# MICROCONTROLLER.net
KiCad netlist of a schematic drawn in Altium Designer
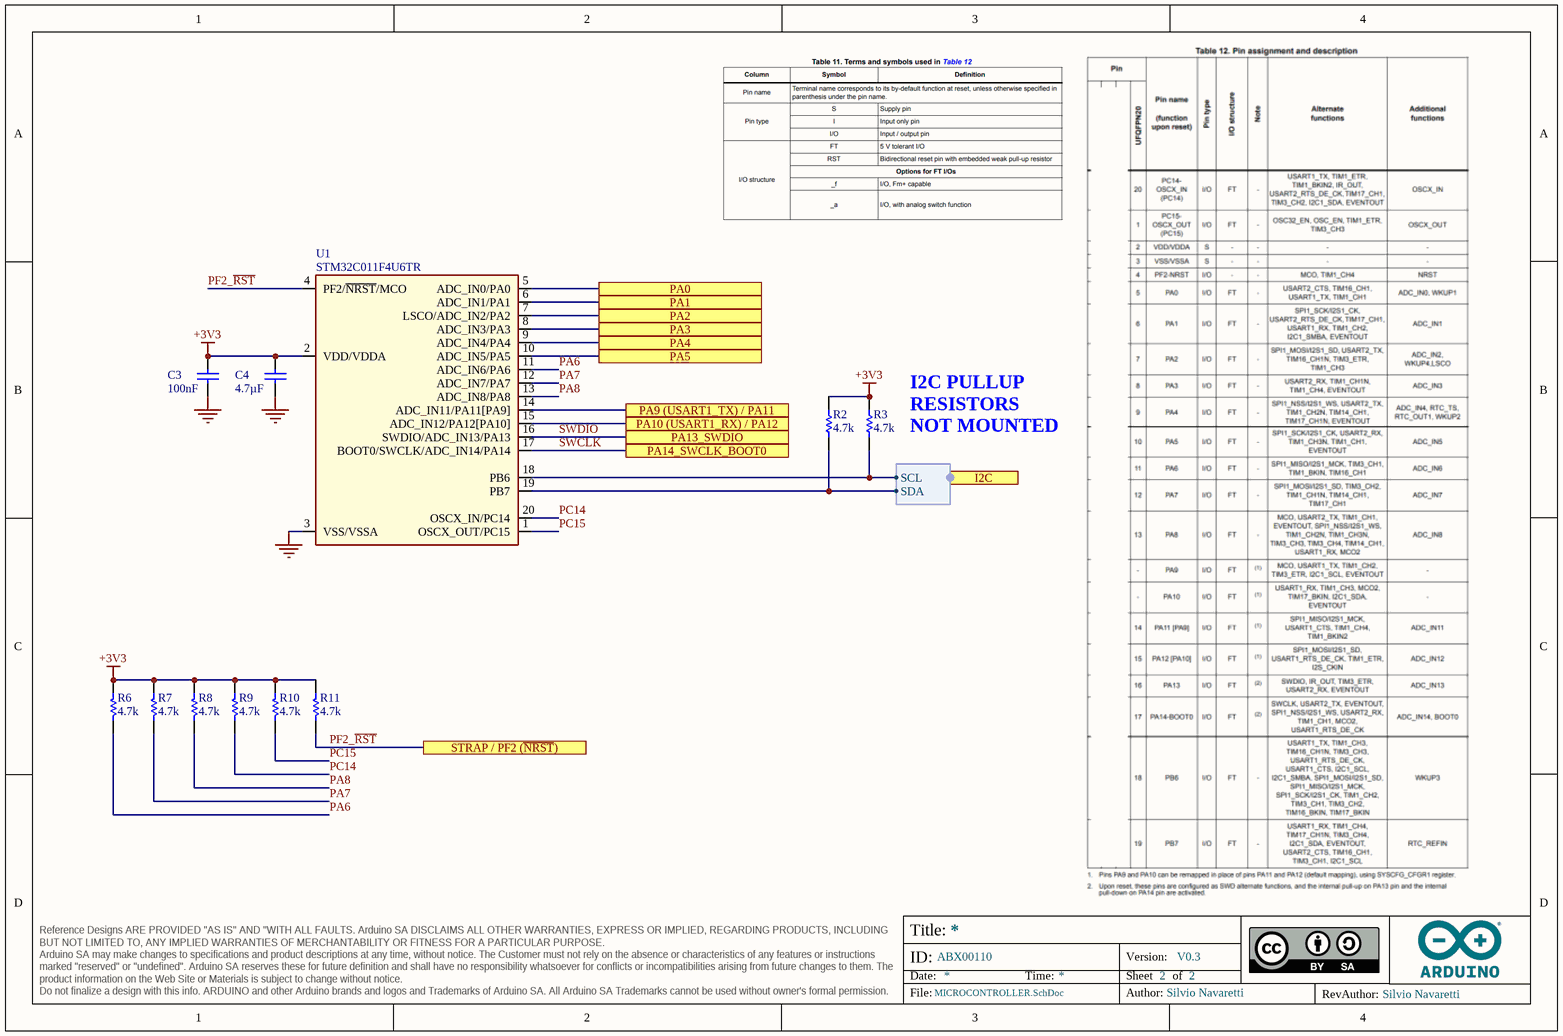
[diagram p0: MICROCONTROLLER.SchDoc]

(export (version "E")
  (design (tool "Eeschema 10.0.6"))
  (components
    (comp (ref "C3")
      (value "100nF")
      (footprint "CAP-0402")
      (description "CAP CHIP 0402 100nF 10% 16V X7R")
      (fields (field (name "MANUFACTURER") "Walsin") (field (name "PART NUMBER") "0402B104K160CT"))
      (libsource (lib "Clean") (part "CAP"))
    )
    (comp (ref "C4")
      (value "4.7µF")
      (footprint "CAP-0603")
      (description "CAP CHIP 0603 4.7uF 10% 16V X5R")
      (fields (field (name "MANUFACTURER") "Murata") (field (name "PART NUMBER") "GRM188R61C475KAAJD"))
      (libsource (lib "Clean") (part "CAP"))
    )
    (comp (ref "R2")
      (value "4.7k")
      (footprint "RES-0402")
      (description "RES CHIP 0402 4k7 1% 1/16W")
      (fields (field (name "PART NUMBER") "RC0402FR-074K7L") (field (name "TOLERANCE") "1%"))
      (libsource (lib "Clean") (part "RES"))
    )
    (comp (ref "R3")
      (value "4.7k")
      (footprint "RES-0402")
      (description "RES CHIP 0402 4k7 1% 1/16W")
      (fields (field (name "PART NUMBER") "RC0402FR-074K7L") (field (name "TOLERANCE") "1%"))
      (libsource (lib "Clean") (part "RES"))
    )
    (comp (ref "R6")
      (value "4.7k")
      (footprint "RES-0402")
      (description "RES CHIP 0402 4k7 1% 1/16W")
      (fields (field (name "POWER") "62.5mW") (field (name "TOLERANCE") "1%"))
      (libsource (lib "Clean") (part "RES"))
    )
    (comp (ref "R7")
      (value "4.7k")
      (footprint "RES-0402")
      (description "RES CHIP 0402 4k7 1% 1/16W")
      (fields (field (name "POWER") "62.5mW") (field (name "TOLERANCE") "1%"))
      (libsource (lib "Clean") (part "RES"))
    )
    (comp (ref "R8")
      (value "4.7k")
      (footprint "RES-0402")
      (description "RES CHIP 0402 4k7 1% 1/16W")
      (fields (field (name "POWER") "62.5mW") (field (name "TOLERANCE") "1%"))
      (libsource (lib "Clean") (part "RES"))
    )
    (comp (ref "R9")
      (value "4.7k")
      (footprint "RES-0402")
      (description "RES CHIP 0402 4k7 1% 1/16W")
      (fields (field (name "POWER") "62.5mW") (field (name "TOLERANCE") "1%"))
      (libsource (lib "Clean") (part "RES"))
    )
    (comp (ref "R10")
      (value "4.7k")
      (footprint "RES-0402")
      (description "RES CHIP 0402 4k7 1% 1/16W")
      (fields (field (name "POWER") "62.5mW") (field (name "TOLERANCE") "1%"))
      (libsource (lib "Clean") (part "RES"))
    )
    (comp (ref "R11")
      (value "4.7k")
      (footprint "RES-0402")
      (description "RES CHIP 0402 4k7 1% 1/16W")
      (fields (field (name "POWER") "62.5mW") (field (name "TOLERANCE") "1%"))
      (libsource (lib "Clean") (part "RES"))
    )
    (comp (ref "U1")
      (value "STM32C011F4U6TR")
      (footprint "UFQFPN20")
      (description "IC Cortex M0, 32b MCU, 32KB Flash, 6KB RAM, VDD 2-3.6V, -40°C to 85°C, QFN20 3x3mm")
      (fields (field (name "MANUFACTURER") "ST Microelectronics"))
      (libsource (lib "Clean") (part "STM32C011F4U6TR"))
    )
  )
  (nets
    (net (code "2") (name "+3V3") (class "Default")
      (node (ref "C3") (pin "1") (pinfunction "1_1") (pintype "passive"))
      (node (ref "C4") (pin "2") (pinfunction "2_2") (pintype "passive"))
      (node (ref "R10") (pin "1") (pinfunction "1_1") (pintype "passive"))
      (node (ref "R11") (pin "1") (pinfunction "1_1") (pintype "passive"))
      (node (ref "R2") (pin "2") (pinfunction "2_2") (pintype "passive"))
      (node (ref "R3") (pin "2") (pinfunction "2_2") (pintype "passive"))
      (node (ref "R6") (pin "1") (pinfunction "1_1") (pintype "passive"))
      (node (ref "R7") (pin "1") (pinfunction "1_1") (pintype "passive"))
      (node (ref "R8") (pin "1") (pinfunction "1_1") (pintype "passive"))
      (node (ref "R9") (pin "1") (pinfunction "1_1") (pintype "passive"))
      (node (ref "U1") (pin "2") (pinfunction "VDD/VDDA_2") (pintype "passive"))
    )
    (net (code "3") (name "/PA0") (class "Default")
      (node (ref "U1") (pin "5") (pinfunction "ADC_IN0/PA0_5") (pintype "passive"))
    )
    (net (code "4") (name "/PA1") (class "Default")
      (node (ref "U1") (pin "6") (pinfunction "ADC_IN1/PA1_6") (pintype "passive"))
    )
    (net (code "5") (name "/PA2") (class "Default")
      (node (ref "U1") (pin "7") (pinfunction "LSCO/ADC_IN2/PA2_7") (pintype "passive"))
    )
    (net (code "6") (name "/PA3") (class "Default")
      (node (ref "U1") (pin "8") (pinfunction "ADC_IN3/PA3_8") (pintype "passive"))
    )
    (net (code "7") (name "/PA4") (class "Default")
      (node (ref "U1") (pin "9") (pinfunction "ADC_IN4/PA4_9") (pintype "passive"))
    )
    (net (code "8") (name "/PA5") (class "Default")
      (node (ref "U1") (pin "10") (pinfunction "ADC_IN5/PA5_10") (pintype "passive"))
    )
    (net (code "9") (name "/PA6") (class "Default")
      (node (ref "R6") (pin "2") (pinfunction "2_2") (pintype "passive"))
      (node (ref "U1") (pin "11") (pinfunction "ADC_IN6/PA6_11") (pintype "passive"))
    )
    (net (code "10") (name "/PA7") (class "Default")
      (node (ref "R7") (pin "2") (pinfunction "2_2") (pintype "passive"))
      (node (ref "U1") (pin "12") (pinfunction "ADC_IN7/PA7_12") (pintype "passive"))
    )
    (net (code "11") (name "/PA8") (class "Default")
      (node (ref "R8") (pin "2") (pinfunction "2_2") (pintype "passive"))
      (node (ref "U1") (pin "13") (pinfunction "ADC_IN8/PA8_13") (pintype "passive"))
    )
    (net (code "12") (name "/PA9 (USART1_TX) {slash} PA11") (class "Default")
      (node (ref "U1") (pin "14") (pinfunction "ADC_IN11/PA11[PA9]_14") (pintype "passive"))
    )
    (net (code "13") (name "/PA10 (USART1_RX) {slash} PA12") (class "Default")
      (node (ref "U1") (pin "15") (pinfunction "ADC_IN12/PA12[PA10]_15") (pintype "passive"))
    )
    (net (code "14") (name "/PC14") (class "Default")
      (node (ref "R9") (pin "2") (pinfunction "2_2") (pintype "passive"))
      (node (ref "U1") (pin "20") (pinfunction "OSCX_IN/PC14_20") (pintype "passive"))
    )
    (net (code "15") (name "/PC15") (class "Default")
      (node (ref "R10") (pin "2") (pinfunction "2_2") (pintype "passive"))
      (node (ref "U1") (pin "1") (pinfunction "OSCX_OUT/PC15_1") (pintype "passive"))
    )
    (net (code "16") (name "/PF2_~{RST}") (class "Default")
      (node (ref "R11") (pin "2") (pinfunction "2_2") (pintype "passive"))
      (node (ref "U1") (pin "4") (pinfunction "PF2/~{NRST}/MCO_4") (pintype "passive"))
    )
    (net (code "17") (name "/SWCLK") (class "Default")
      (node (ref "U1") (pin "17") (pinfunction "BOOT0/SWCLK/ADC_IN14/PA14_17") (pintype "passive"))
    )
    (net (code "18") (name "/SWDIO") (class "Default")
      (node (ref "U1") (pin "16") (pinfunction "SWDIO/ADC_IN13/PA13_16") (pintype "passive"))
    )
    (net (code "20") (name "GND") (class "Default")
      (node (ref "C3") (pin "2") (pinfunction "2_2") (pintype "passive"))
      (node (ref "C4") (pin "1") (pinfunction "1_1") (pintype "passive"))
      (node (ref "U1") (pin "3") (pinfunction "VSS/VSSA_3") (pintype "passive"))
    )
    (net (code "21") (name "Net-(U1-PB6)") (class "Default")
      (node (ref "R3") (pin "1") (pinfunction "1_1") (pintype "passive"))
      (node (ref "U1") (pin "18") (pinfunction "PB6_18") (pintype "passive"))
    )
    (net (code "22") (name "Net-(U1-PB7)") (class "Default")
      (node (ref "R2") (pin "1") (pinfunction "1_1") (pintype "passive"))
      (node (ref "U1") (pin "19") (pinfunction "PB7_19") (pintype "passive"))
    )
  )
)
